# sFMC98_v1.net
KiCad netlist of a schematic drawn in Altium Designer
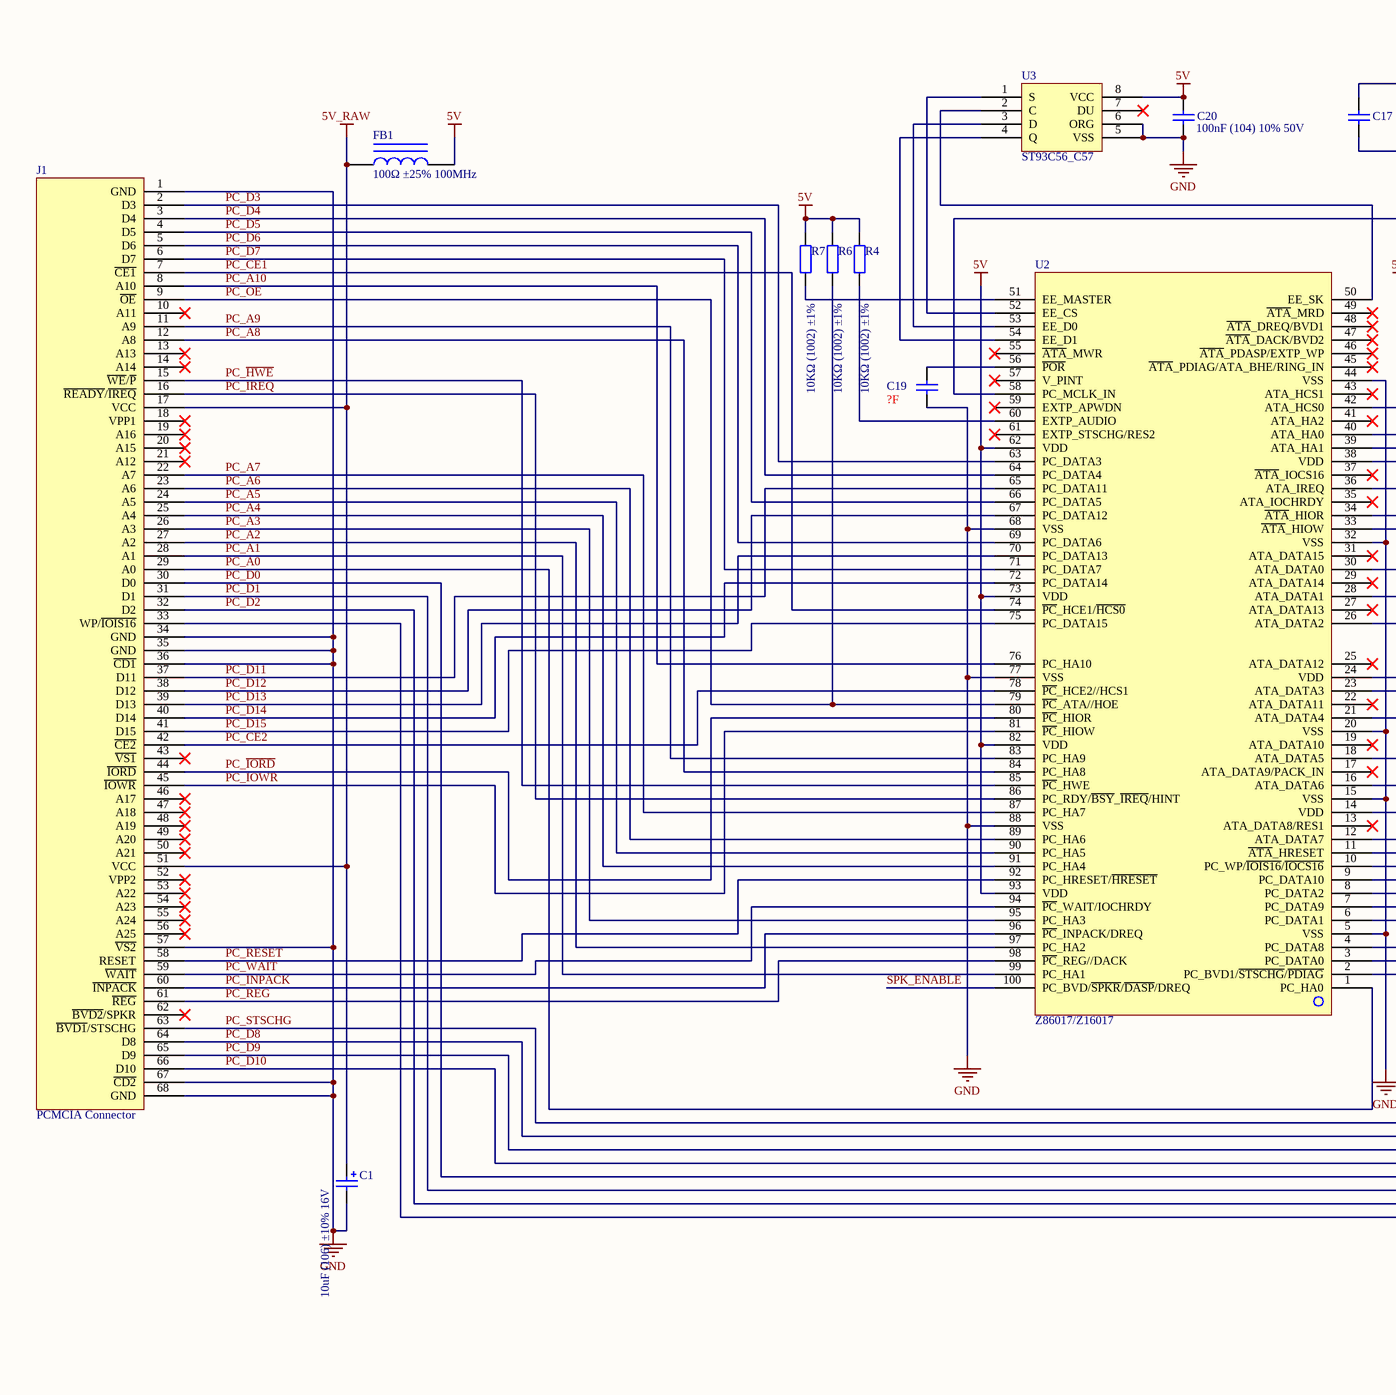
[diagram p0: sFMC98_v1.SchDoc, left]
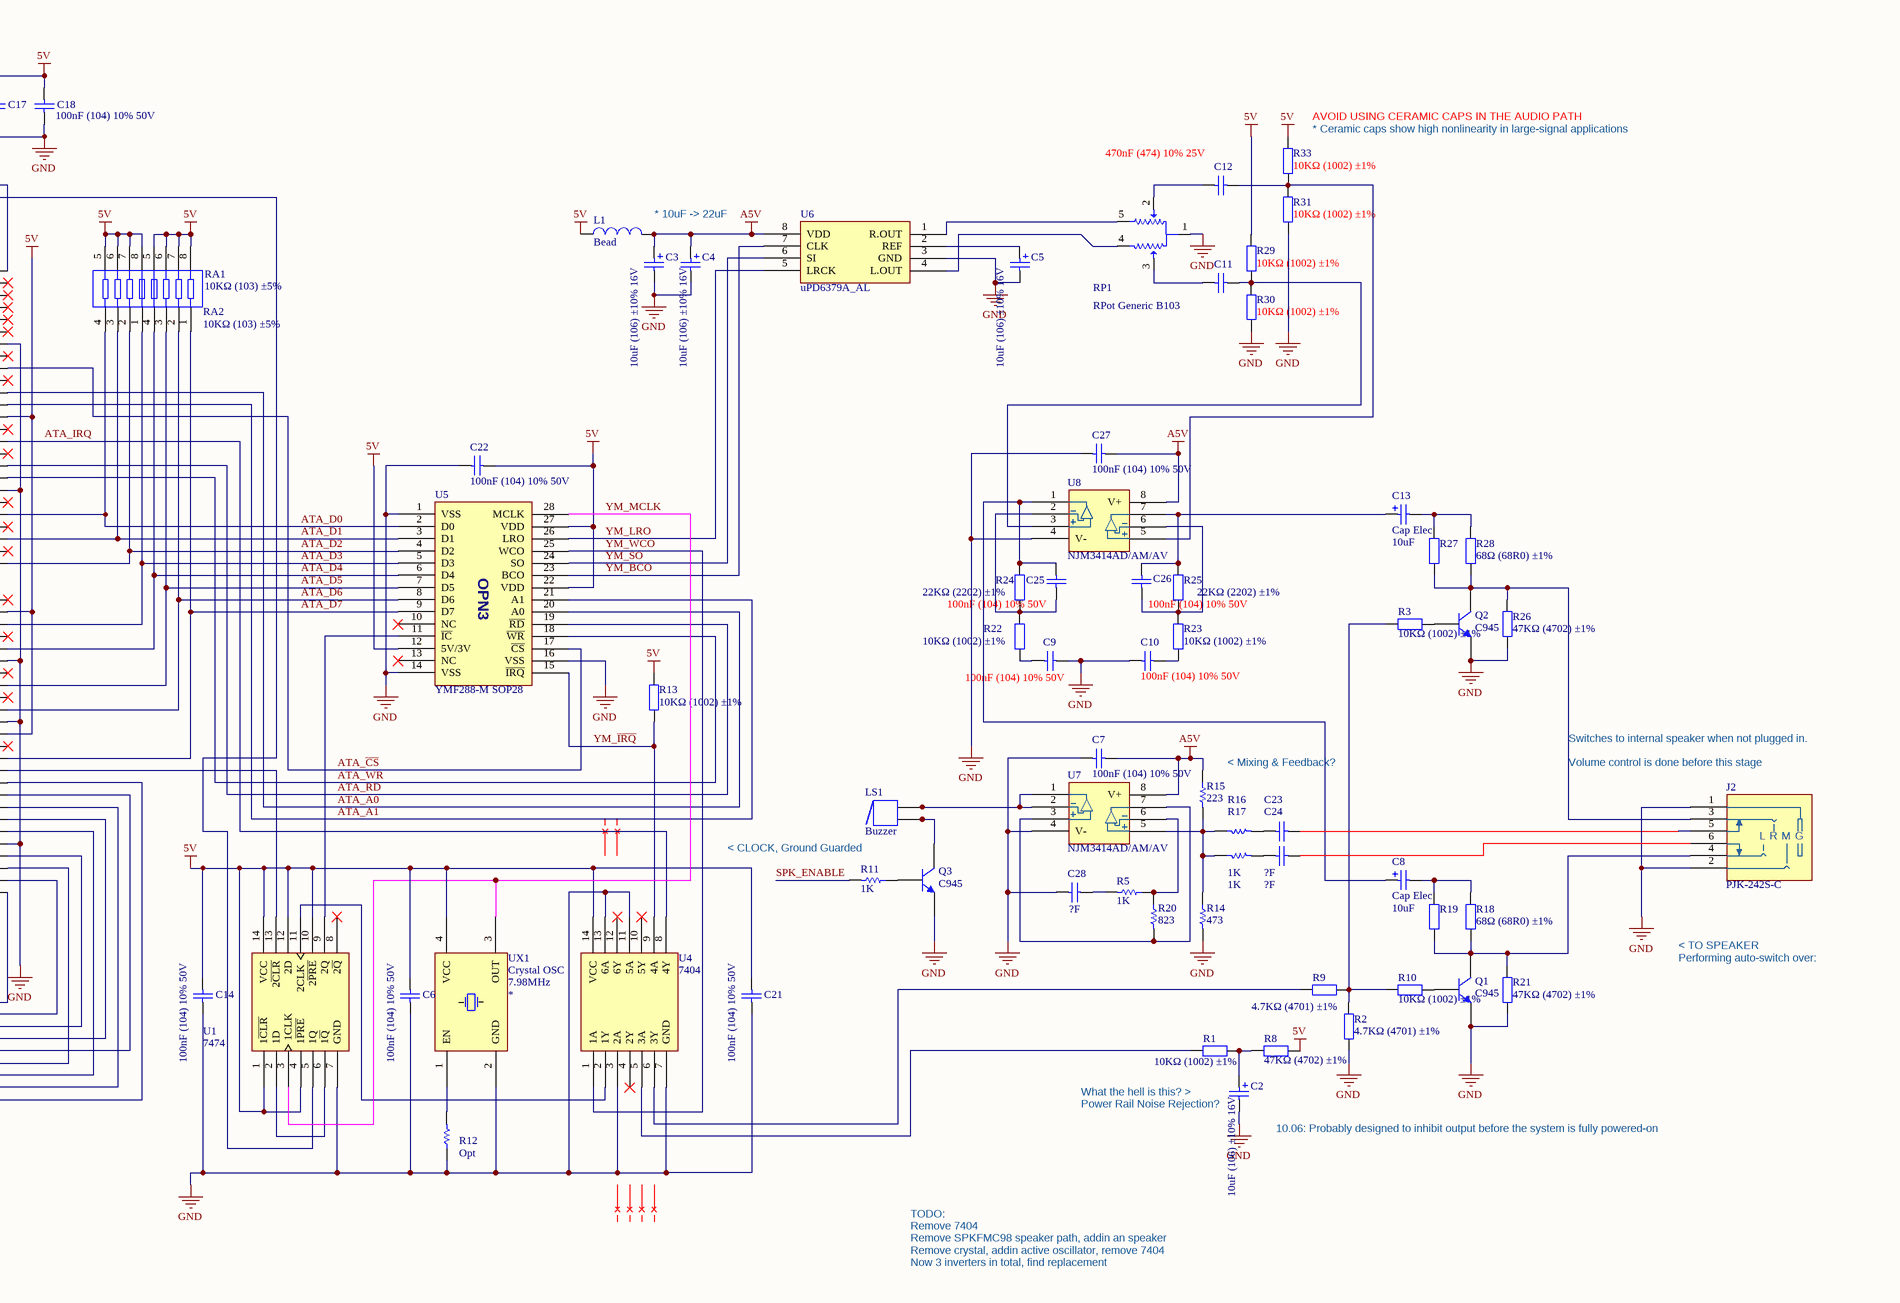
[diagram p1: sFMC98_v1.SchDoc, right]

(export (version "E")
  (design (tool "Eeschema 10.0.6"))
  (components
    (comp (ref "C1")
      (value "10uF (106) ±10% 16V")
      (footprint "CASE-A_3216")
      (description "钽电容")
      (libsource (lib "JLC_Cap") (part "3216 10uF (106) 10% 16V"))
    )
    (comp (ref "C2")
      (value "10uF (106) ±10% 16V")
      (footprint "CASE-A_3216")
      (description "钽电容")
      (libsource (lib "JLC_Cap") (part "3216 10uF (106) 10% 16V"))
    )
    (comp (ref "C3")
      (value "10uF (106) ±10% 16V")
      (footprint "CASE-A_3216")
      (description "钽电容")
      (libsource (lib "JLC_Cap") (part "3216 10uF (106) 10% 16V"))
    )
    (comp (ref "C4")
      (value "10uF (106) ±10% 16V")
      (footprint "CASE-A_3216")
      (description "钽电容")
      (libsource (lib "JLC_Cap") (part "3216 10uF (106) 10% 16V"))
    )
    (comp (ref "C5")
      (value "10uF (106) ±10% 16V")
      (footprint "CASE-A_3216")
      (description "钽电容")
      (libsource (lib "JLC_Cap") (part "3216 10uF (106) 10% 16V"))
    )
    (comp (ref "C6")
      (value "100nF (104) 10% 50V")
      (footprint "0603_C")
      (description "贴片电容")
      (libsource (lib "JLC_Cap") (part "0603 100nF (104) 10% 50V"))
    )
    (comp (ref "C7")
      (value "100nF (104) 10% 50V")
      (footprint "0603_C")
      (description "贴片电容")
      (libsource (lib "JLC_Cap") (part "0603 100nF (104) 10% 50V"))
    )
    (comp (ref "C8")
      (value "Cap Elec")
      (footprint "C-RB-4_5MM_Cutout")
      (description "Polarized Capacitor (Surface Mount)")
      (fields (field (name "ALTIUM_VALUE") "10uF") (field (name "PUBLISHER") "Altium Limited"))
      (libsource (lib "DiscreteRF") (part "Cap Pol3"))
    )
    (comp (ref "C9")
      (value "100nF (104) 10% 50V")
      (footprint "0603_C")
      (description "贴片电容")
      (libsource (lib "JLC_Cap") (part "0603 100nF (104) 10% 50V"))
    )
    (comp (ref "C10")
      (value "100nF (104) 10% 50V")
      (footprint "0603_C")
      (description "贴片电容")
      (libsource (lib "JLC_Cap") (part "0603 100nF (104) 10% 50V"))
    )
    (comp (ref "C11")
      (value "470nF (474) 10% 25V")
      (footprint "0603_C")
      (description "贴片电容")
      (libsource (lib "JLC_Cap") (part "0603 470nF (474) 10% 25V"))
    )
    (comp (ref "C12")
      (value "470nF (474) 10% 25V")
      (footprint "0603_C")
      (description "贴片电容")
      (libsource (lib "JLC_Cap") (part "0603 470nF (474) 10% 25V"))
    )
    (comp (ref "C13")
      (value "Cap Elec")
      (footprint "C-RB-4_5MM_Cutout")
      (description "Polarized Capacitor (Surface Mount)")
      (fields (field (name "ALTIUM_VALUE") "10uF") (field (name "PUBLISHER") "Altium Limited"))
      (libsource (lib "DiscreteRF") (part "Cap Pol3"))
    )
    (comp (ref "C14")
      (value "100nF (104) 10% 50V")
      (footprint "0603_C")
      (description "贴片电容")
      (libsource (lib "JLC_Cap") (part "0603 100nF (104) 10% 50V"))
    )
    (comp (ref "C17")
      (value "100nF (104) 10% 50V")
      (footprint "0603_C")
      (description "贴片电容")
      (libsource (lib "JLC_Cap") (part "0603 100nF (104) 10% 50V"))
    )
    (comp (ref "C18")
      (value "100nF (104) 10% 50V")
      (footprint "0603_C")
      (description "贴片电容")
      (libsource (lib "JLC_Cap") (part "0603 100nF (104) 10% 50V"))
    )
    (comp (ref "C19")
      (value "?F")
      (footprint "CEIA0603X04N")
      (description "Capacitor")
      (fields (field (name "Comment") "Cap") (field (name "PUBLISHER") "Altium Limited"))
      (libsource (lib "DiscreteRF") (part "Cap"))
    )
    (comp (ref "C20")
      (value "100nF (104) 10% 50V")
      (footprint "0603_C")
      (description "贴片电容")
      (libsource (lib "JLC_Cap") (part "0603 100nF (104) 10% 50V"))
    )
    (comp (ref "C21")
      (value "100nF (104) 10% 50V")
      (footprint "0603_C")
      (description "贴片电容")
      (libsource (lib "JLC_Cap") (part "0603 100nF (104) 10% 50V"))
    )
    (comp (ref "C22")
      (value "100nF (104) 10% 50V")
      (footprint "0603_C")
      (description "贴片电容")
      (libsource (lib "JLC_Cap") (part "0603 100nF (104) 10% 50V"))
    )
    (comp (ref "C23")
      (value "?F")
      (footprint "CEIA0603X04N")
      (description "Capacitor")
      (fields (field (name "Comment") "Cap") (field (name "PUBLISHER") "Altium Limited"))
      (libsource (lib "DiscreteRF") (part "Cap"))
    )
    (comp (ref "C24")
      (value "?F")
      (footprint "CEIA0603X04N")
      (description "Capacitor")
      (fields (field (name "Comment") "Cap") (field (name "PUBLISHER") "Altium Limited"))
      (libsource (lib "DiscreteRF") (part "Cap"))
    )
    (comp (ref "C25")
      (value "100nF (104) 10% 50V")
      (footprint "0603_C")
      (description "贴片电容")
      (libsource (lib "JLC_Cap") (part "0603 100nF (104) 10% 50V"))
    )
    (comp (ref "C26")
      (value "100nF (104) 10% 50V")
      (footprint "0603_C")
      (description "贴片电容")
      (libsource (lib "JLC_Cap") (part "0603 100nF (104) 10% 50V"))
    )
    (comp (ref "C27")
      (value "100nF (104) 10% 50V")
      (footprint "0603_C")
      (description "贴片电容")
      (libsource (lib "JLC_Cap") (part "0603 100nF (104) 10% 50V"))
    )
    (comp (ref "C28")
      (value "?F")
      (footprint "CEIA0603X04N")
      (description "Capacitor")
      (fields (field (name "Comment") "Cap") (field (name "PUBLISHER") "Altium Limited"))
      (libsource (lib "DiscreteRF") (part "Cap"))
    )
    (comp (ref "FB1")
      (value "100Ω ±25% 100MHz")
      (footprint "0805_L")
      (description "贴片磁珠")
      (libsource (lib "JLC_IUD") (part "0805 100Ω 25% 100MHz"))
    )
    (comp (ref "J1")
      (value "PCMCIA Connector")
      (footprint "PCF-SMT-K1")
      (libsource (lib "PrimaryLIB1") (part "PCMCIA_Conn"))
    )
    (comp (ref "J2")
      (value "PJK-242S-C")
      (footprint "PJK-242S-C")
      (description "2.5mm Headphone Jack")
      (libsource (lib "PrimaryLIB1") (part "PJK-242S-C"))
    )
    (comp (ref "L1")
      (value "Bead")
      (footprint "L2012X10N_LQW21")
      (description "Inductor")
      (fields (field (name "PUBLISHER") "Altium Limited"))
      (libsource (lib "DiscreteRF") (part "Inductor"))
    )
    (comp (ref "LS1")
      (value "Buzzer")
      (footprint "SPK_PCB_MOUNT")
      (description "Magnetic Transducer Buzzer")
      (fields (field (name "PUBLISHER") "Altium Limited"))
      (libsource (lib "Miscellaneous Devices") (part "Buzzer"))
    )
    (comp (ref "Q1")
      (value "C945")
      (footprint "SOT-23(SOT-23-3)")
      (description "三极管")
      (libsource (lib "JLC_Transistor_NPN") (part "SOT-23 SS8050 Y1"))
    )
    (comp (ref "Q2")
      (value "C945")
      (footprint "SOT-23(SOT-23-3)")
      (description "三极管")
      (libsource (lib "JLC_Transistor_NPN") (part "SOT-23 SS8050 Y1"))
    )
    (comp (ref "Q3")
      (value "C945")
      (footprint "SOT-23(SOT-23-3)")
      (description "三极管")
      (libsource (lib "JLC_Transistor_NPN") (part "SOT-23 SS8050 Y1"))
    )
    (comp (ref "R1")
      (value "10KΩ (1002) ±1%")
      (footprint "0603_R")
      (description "贴片电阻")
      (libsource (lib "") (part "0603 10KΩ (1002) 1%_1"))
    )
    (comp (ref "R2")
      (value "4.7KΩ (4701) ±1%")
      (footprint "0603_R")
      (description "贴片电阻")
      (libsource (lib "JLC_RES") (part "0603 4.7KΩ (4701) 1%"))
    )
    (comp (ref "R3")
      (value "10KΩ (1002) ±1%")
      (footprint "0603_R")
      (description "贴片电阻")
      (libsource (lib "") (part "0603 10KΩ (1002) 1%_1"))
    )
    (comp (ref "R4")
      (value "10KΩ (1002) ±1%")
      (footprint "0603_R")
      (description "贴片电阻")
      (libsource (lib "JLC_RES") (part "0603 10KΩ (1002) 1%"))
    )
    (comp (ref "R5")
      (value "1K")
      (footprint "REIA0603X04N")
      (description "Resistor")
      (fields (field (name "Comment") "Res1") (field (name "PUBLISHER") "Altium Limited"))
      (libsource (lib "DiscreteRF") (part "Res1"))
    )
    (comp (ref "R6")
      (value "10KΩ (1002) ±1%")
      (footprint "0603_R")
      (description "贴片电阻")
      (libsource (lib "JLC_RES") (part "0603 10KΩ (1002) 1%"))
    )
    (comp (ref "R7")
      (value "10KΩ (1002) ±1%")
      (footprint "0603_R")
      (description "贴片电阻")
      (libsource (lib "JLC_RES") (part "0603 10KΩ (1002) 1%"))
    )
    (comp (ref "R8")
      (value "47KΩ (4702) ±1%")
      (footprint "0603_R")
      (description "贴片电阻")
      (libsource (lib "") (part "0603 47KΩ (4702) 1%_1"))
    )
    (comp (ref "R9")
      (value "4.7KΩ (4701) ±1%")
      (footprint "0603_R")
      (description "贴片电阻")
      (libsource (lib "") (part "0603 4.7KΩ (4701) 1%_1"))
    )
    (comp (ref "R10")
      (value "10KΩ (1002) ±1%")
      (footprint "0603_R")
      (description "贴片电阻")
      (libsource (lib "") (part "0603 10KΩ (1002) 1%_1"))
    )
    (comp (ref "R11")
      (value "1K")
      (footprint "REIA0603X04N")
      (description "Resistor")
      (fields (field (name "Comment") "Res1") (field (name "PUBLISHER") "Altium Limited"))
      (libsource (lib "DiscreteRF") (part "Res1"))
    )
    (comp (ref "R12")
      (value "Opt")
      (footprint "REIA0603X04N")
      (description "Resistor")
      (fields (field (name "Comment") "Res1") (field (name "PUBLISHER") "Altium Limited"))
      (libsource (lib "DiscreteRF") (part "Res1"))
    )
    (comp (ref "R13")
      (value "10KΩ (1002) ±1%")
      (footprint "0603_R")
      (description "贴片电阻")
      (libsource (lib "JLC_RES") (part "0603 10KΩ (1002) 1%"))
    )
    (comp (ref "R14")
      (value "473")
      (footprint "REIA0603X04N")
      (description "Resistor")
      (fields (field (name "Comment") "Res1") (field (name "PUBLISHER") "Altium Limited"))
      (libsource (lib "DiscreteRF") (part "Res1"))
    )
    (comp (ref "R15")
      (value "223")
      (footprint "REIA0603X04N")
      (description "Resistor")
      (fields (field (name "Comment") "Res1") (field (name "PUBLISHER") "Altium Limited"))
      (libsource (lib "DiscreteRF") (part "Res1"))
    )
    (comp (ref "R16")
      (value "1K")
      (footprint "REIA0603X04N")
      (description "Resistor")
      (fields (field (name "Comment") "Res1") (field (name "PUBLISHER") "Altium Limited"))
      (libsource (lib "DiscreteRF") (part "Res1"))
    )
    (comp (ref "R17")
      (value "1K")
      (footprint "REIA0603X04N")
      (description "Resistor")
      (fields (field (name "Comment") "Res1") (field (name "PUBLISHER") "Altium Limited"))
      (libsource (lib "DiscreteRF") (part "Res1"))
    )
    (comp (ref "R18")
      (value "68Ω (68R0) ±1%")
      (footprint "0603_R")
      (description "贴片电阻")
      (libsource (lib "JLC_RES") (part "0603 68Ω (68R0) 1%"))
    )
    (comp (ref "R19")
      (value "68Ω (68R0) ±1%")
      (footprint "0603_R")
      (description "贴片电阻")
      (libsource (lib "JLC_RES") (part "0603 68Ω (68R0) 1%"))
    )
    (comp (ref "R20")
      (value "823")
      (footprint "REIA0603X04N")
      (description "Resistor")
      (fields (field (name "Comment") "Res1") (field (name "PUBLISHER") "Altium Limited"))
      (libsource (lib "DiscreteRF") (part "Res1"))
    )
    (comp (ref "R21")
      (value "47KΩ (4702) ±1%")
      (footprint "0603_R")
      (description "贴片电阻")
      (libsource (lib "JLC_RES") (part "0603 47KΩ (4702) 1%"))
    )
    (comp (ref "R22")
      (value "10KΩ (1002) ±1%")
      (footprint "0603_R")
      (description "贴片电阻")
      (libsource (lib "JLC_RES") (part "0603 10KΩ (1002) 1%"))
    )
    (comp (ref "R23")
      (value "10KΩ (1002) ±1%")
      (footprint "0603_R")
      (description "贴片电阻")
      (libsource (lib "JLC_RES") (part "0603 10KΩ (1002) 1%"))
    )
    (comp (ref "R24")
      (value "22KΩ (2202) ±1%")
      (footprint "0603_R")
      (description "贴片电阻")
      (libsource (lib "JLC_RES") (part "0603 22KΩ (2202) 1%"))
    )
    (comp (ref "R25")
      (value "22KΩ (2202) ±1%")
      (footprint "0603_R")
      (description "贴片电阻")
      (libsource (lib "JLC_RES") (part "0603 22KΩ (2202) 1%"))
    )
    (comp (ref "R26")
      (value "47KΩ (4702) ±1%")
      (footprint "0603_R")
      (description "贴片电阻")
      (libsource (lib "JLC_RES") (part "0603 47KΩ (4702) 1%"))
    )
    (comp (ref "R27")
      (value "68Ω (68R0) ±1%")
      (footprint "0603_R")
      (description "贴片电阻")
      (libsource (lib "JLC_RES") (part "0603 68Ω (68R0) 1%"))
    )
    (comp (ref "R28")
      (value "68Ω (68R0) ±1%")
      (footprint "0603_R")
      (description "贴片电阻")
      (libsource (lib "JLC_RES") (part "0603 68Ω (68R0) 1%"))
    )
    (comp (ref "R29")
      (value "10KΩ (1002) ±1%")
      (footprint "0603_R")
      (description "贴片电阻")
      (libsource (lib "JLC_RES") (part "0603 10KΩ (1002) 1%"))
    )
    (comp (ref "R30")
      (value "10KΩ (1002) ±1%")
      (footprint "0603_R")
      (description "贴片电阻")
      (libsource (lib "JLC_RES") (part "0603 10KΩ (1002) 1%"))
    )
    (comp (ref "R31")
      (value "10KΩ (1002) ±1%")
      (footprint "0603_R")
      (description "贴片电阻")
      (libsource (lib "JLC_RES") (part "0603 10KΩ (1002) 1%"))
    )
    (comp (ref "R33")
      (value "10KΩ (1002) ±1%")
      (footprint "0603_R")
      (description "贴片电阻")
      (libsource (lib "JLC_RES") (part "0603 10KΩ (1002) 1%"))
    )
    (comp (ref "RA1")
      (value "10KΩ (103) ±5%")
      (footprint "0603_Rx4")
      (description "贴片排阻")
      (libsource (lib "JLC_RES") (part "0603*4  10KΩ (103) 5%"))
    )
    (comp (ref "RA2")
      (value "10KΩ (103) ±5%")
      (footprint "0603_Rx4")
      (description "贴片排阻")
      (libsource (lib "JLC_RES") (part "0603*4  10KΩ (103) 5%"))
    )
    (comp (ref "RP1")
      (value "RPot Generic B103")
      (footprint "RPot_RK10J12E_ALPS")
      (libsource (lib "PrimaryLIB1") (part "RPot_Generic_Bxxx"))
    )
    (comp (ref "U1")
      (value "7474")
      (footprint "TSSOP14_TSOP65P640X120-14N")
      (description "Dual D-Type Positive-Edge-Triggered Flip-Flops With Preset And Clear")
      (libsource (lib "7400") (part "7474_J_N_1"))
    )
    (comp (ref "U2")
      (value "Z86017/Z16017")
      (footprint "VQFP100_TSQFP50P1600X1600X160-100N")
      (libsource (lib "PrimaryLIB1") (part "ZX6017"))
    )
    (comp (ref "U3")
      (value "ST93C56_C57")
      (footprint "SOIC-8 NB")
      (description "2K (128 x 16 or 256 x 8) SERIAL MICROWIRE EEPROM")
      (libsource (lib "PrimaryLIB1") (part "ST93C56_C57"))
    )
    (comp (ref "U4")
      (value "7404")
      (footprint "TSSOP14_TSOP65P640X120-14N")
      (description "Hex Inverter")
      (libsource (lib "7400") (part "7404_J_N_1"))
    )
    (comp (ref "U5")
      (value "YMF288-M SOP28")
      (footprint "SOP127P1030X265-28N")
      (libsource (lib "Audio") (part "YMF288_M"))
    )
    (comp (ref "U6")
      (value "uPD6379A_AL")
      (footprint "DMP8_SOIC127P680X175-8N")
      (description "2-CHANNEL 16-BIT D/A CONVERTER FOR AUDIO APPLICATION")
      (libsource (lib "Audio") (part "uPD6379A_AL"))
    )
    (comp (ref "U7")
      (value "NJM3414AD/AM/AV")
      (footprint "DMP8_SOIC127P680X175-8N")
      (description "Single-Supply Dual High Current Operational Amplifier")
      (libsource (lib "PrimaryLIB1") (part "NJM3414AD_AM_AV_1"))
    )
    (comp (ref "U8")
      (value "NJM3414AD/AM/AV")
      (footprint "DMP8_SOIC127P680X175-8N")
      (description "Single-Supply Dual High Current Operational Amplifier")
      (libsource (lib "PrimaryLIB1") (part "NJM3414AD_AM_AV_1"))
    )
    (comp (ref "UX1")
      (value "Crystal OSC")
      (footprint "SMD-3225_4P")
      (fields (field (name "FREQ") "7.98MHz") (field (name "TYPE") "*"))
      (libsource (lib "PrimaryLIB1") (part "XTAL_OSC"))
    )
  )
  (nets
    (net (code "1") (name "/ATA_A0") (class "Default")
      (node (ref "U2") (pin "40") (pinfunction "ATA_HA0_40") (pintype "passive"))
      (node (ref "U5") (pin "20") (pinfunction "A0_20") (pintype "passive"))
    )
    (net (code "2") (name "/ATA_A1") (class "Default")
      (node (ref "U2") (pin "39") (pinfunction "ATA_HA1_39") (pintype "passive"))
      (node (ref "U5") (pin "21") (pinfunction "A1_21") (pintype "passive"))
    )
    (net (code "3") (name "/ATA_D0") (class "Default")
      (node (ref "RA2") (pin "4") (pinfunction "4_4") (pintype "passive"))
      (node (ref "U2") (pin "30") (pinfunction "ATA_DATA0_30") (pintype "passive"))
      (node (ref "U5") (pin "2") (pinfunction "D0_2") (pintype "passive"))
    )
    (net (code "4") (name "/ATA_D1") (class "Default")
      (node (ref "RA2") (pin "3") (pinfunction "3_3") (pintype "passive"))
      (node (ref "U2") (pin "28") (pinfunction "ATA_DATA1_28") (pintype "passive"))
      (node (ref "U5") (pin "3") (pinfunction "D1_3") (pintype "passive"))
    )
    (net (code "5") (name "/ATA_D2") (class "Default")
      (node (ref "RA2") (pin "2") (pinfunction "2_2") (pintype "passive"))
      (node (ref "U2") (pin "26") (pinfunction "ATA_DATA2_26") (pintype "passive"))
      (node (ref "U5") (pin "4") (pinfunction "D2_4") (pintype "passive"))
    )
    (net (code "6") (name "/ATA_D3") (class "Default")
      (node (ref "RA2") (pin "1") (pinfunction "1_1") (pintype "passive"))
      (node (ref "U2") (pin "23") (pinfunction "ATA_DATA3_23") (pintype "passive"))
      (node (ref "U5") (pin "5") (pinfunction "D3_5") (pintype "passive"))
    )
    (net (code "7") (name "/ATA_D4") (class "Default")
      (node (ref "RA1") (pin "4") (pinfunction "4_4") (pintype "passive"))
      (node (ref "U2") (pin "21") (pinfunction "ATA_DATA4_21") (pintype "passive"))
      (node (ref "U5") (pin "6") (pinfunction "D4_6") (pintype "passive"))
    )
    (net (code "8") (name "/ATA_D5") (class "Default")
      (node (ref "RA1") (pin "3") (pinfunction "3_3") (pintype "passive"))
      (node (ref "U2") (pin "18") (pinfunction "ATA_DATA5_18") (pintype "passive"))
      (node (ref "U5") (pin "7") (pinfunction "D5_7") (pintype "passive"))
    )
    (net (code "9") (name "/ATA_D6") (class "Default")
      (node (ref "RA1") (pin "2") (pinfunction "2_2") (pintype "passive"))
      (node (ref "U2") (pin "16") (pinfunction "ATA_DATA6_16") (pintype "passive"))
      (node (ref "U5") (pin "8") (pinfunction "D6_8") (pintype "passive"))
    )
    (net (code "10") (name "/ATA_D7") (class "Default")
      (node (ref "RA1") (pin "1") (pinfunction "1_1") (pintype "passive"))
      (node (ref "U2") (pin "12") (pinfunction "ATA_DATA7_12") (pintype "passive"))
      (node (ref "U5") (pin "9") (pinfunction "D7_9") (pintype "passive"))
    )
    (net (code "11") (name "/ATA_IRQ") (class "Default")
      (node (ref "U2") (pin "36") (pinfunction "ATA_IREQ_36") (pintype "passive"))
      (node (ref "U4") (pin "8") (pinfunction "4Y_8") (pintype "passive"))
    )
    (net (code "12") (name "/ATA_~{CS}") (class "Default")
      (node (ref "U2") (pin "42") (pinfunction "ATA_HCS0_42") (pintype "passive"))
      (node (ref "U5") (pin "17") (pinfunction "~{CS}_17") (pintype "passive"))
    )
    (net (code "13") (name "/ATA_~{RD}") (class "Default")
      (node (ref "U2") (pin "34") (pinfunction "~{ATA}_HIOR_34") (pintype "passive"))
      (node (ref "U5") (pin "19") (pinfunction "~{RD}_19") (pintype "passive"))
    )
    (net (code "14") (name "/ATA_~{WR}") (class "Default")
      (node (ref "U2") (pin "33") (pinfunction "~{ATA}_HIOW_33") (pintype "passive"))
      (node (ref "U5") (pin "18") (pinfunction "~{WR}_18") (pintype "passive"))
    )
    (net (code "15") (name "/PC_A0") (class "Default")
      (node (ref "J1") (pin "29") (pinfunction "A0_29") (pintype "passive"))
      (node (ref "U2") (pin "1") (pinfunction "PC_HA0_1") (pintype "passive"))
    )
    (net (code "16") (name "/PC_A1") (class "Default")
      (node (ref "J1") (pin "28") (pinfunction "A1_28") (pintype "passive"))
      (node (ref "U2") (pin "99") (pinfunction "PC_HA1_99") (pintype "passive"))
    )
    (net (code "17") (name "/PC_A2") (class "Default")
      (node (ref "J1") (pin "27") (pinfunction "A2_27") (pintype "passive"))
      (node (ref "U2") (pin "97") (pinfunction "PC_HA2_97") (pintype "passive"))
    )
    (net (code "18") (name "/PC_A3") (class "Default")
      (node (ref "J1") (pin "26") (pinfunction "A3_26") (pintype "passive"))
      (node (ref "U2") (pin "95") (pinfunction "PC_HA3_95") (pintype "passive"))
    )
    (net (code "19") (name "/PC_A4") (class "Default")
      (node (ref "J1") (pin "25") (pinfunction "A4_25") (pintype "passive"))
      (node (ref "U2") (pin "91") (pinfunction "PC_HA4_91") (pintype "passive"))
    )
    (net (code "20") (name "/PC_A5") (class "Default")
      (node (ref "J1") (pin "24") (pinfunction "A5_24") (pintype "passive"))
      (node (ref "U2") (pin "90") (pinfunction "PC_HA5_90") (pintype "passive"))
    )
    (net (code "21") (name "/PC_A6") (class "Default")
      (node (ref "J1") (pin "23") (pinfunction "A6_23") (pintype "passive"))
      (node (ref "U2") (pin "89") (pinfunction "PC_HA6_89") (pintype "passive"))
    )
    (net (code "22") (name "/PC_A7") (class "Default")
      (node (ref "J1") (pin "22") (pinfunction "A7_22") (pintype "passive"))
      (node (ref "U2") (pin "87") (pinfunction "PC_HA7_87") (pintype "passive"))
    )
    (net (code "23") (name "/PC_A8") (class "Default")
      (node (ref "J1") (pin "12") (pinfunction "A8_12") (pintype "passive"))
      (node (ref "U2") (pin "84") (pinfunction "PC_HA8_84") (pintype "passive"))
    )
    (net (code "24") (name "/PC_A9") (class "Default")
      (node (ref "J1") (pin "11") (pinfunction "A9_11") (pintype "passive"))
      (node (ref "U2") (pin "83") (pinfunction "PC_HA9_83") (pintype "passive"))
    )
    (net (code "25") (name "/PC_A10") (class "Default")
      (node (ref "J1") (pin "8") (pinfunction "A10_8") (pintype "passive"))
      (node (ref "U2") (pin "76") (pinfunction "PC_HA10_76") (pintype "passive"))
    )
    (net (code "26") (name "/PC_D0") (class "Default")
      (node (ref "J1") (pin "30") (pinfunction "D0_30") (pintype "passive"))
      (node (ref "U2") (pin "3") (pinfunction "PC_DATA0_3") (pintype "passive"))
    )
    (net (code "27") (name "/PC_D1") (class "Default")
      (node (ref "J1") (pin "31") (pinfunction "D1_31") (pintype "passive"))
      (node (ref "U2") (pin "6") (pinfunction "PC_DATA1_6") (pintype "passive"))
    )
    (net (code "28") (name "/PC_D2") (class "Default")
      (node (ref "J1") (pin "32") (pinfunction "D2_32") (pintype "passive"))
      (node (ref "U2") (pin "8") (pinfunction "PC_DATA2_8") (pintype "passive"))
    )
    (net (code "29") (name "/PC_D3") (class "Default")
      (node (ref "J1") (pin "2") (pinfunction "D3_2") (pintype "passive"))
      (node (ref "U2") (pin "63") (pinfunction "PC_DATA3_63") (pintype "passive"))
    )
    (net (code "30") (name "/PC_D4") (class "Default")
      (node (ref "J1") (pin "3") (pinfunction "D4_3") (pintype "passive"))
      (node (ref "U2") (pin "64") (pinfunction "PC_DATA4_64") (pintype "passive"))
    )
    (net (code "31") (name "/PC_D5") (class "Default")
      (node (ref "J1") (pin "4") (pinfunction "D5_4") (pintype "passive"))
      (node (ref "U2") (pin "66") (pinfunction "PC_DATA5_66") (pintype "passive"))
    )
    (net (code "32") (name "/PC_D6") (class "Default")
      (node (ref "J1") (pin "5") (pinfunction "D6_5") (pintype "passive"))
      (node (ref "U2") (pin "69") (pinfunction "PC_DATA6_69") (pintype "passive"))
    )
    (net (code "33") (name "/PC_D7") (class "Default")
      (node (ref "J1") (pin "6") (pinfunction "D7_6") (pintype "passive"))
      (node (ref "U2") (pin "71") (pinfunction "PC_DATA7_71") (pintype "passive"))
    )
    (net (code "34") (name "/PC_D8") (class "Default")
      (node (ref "J1") (pin "64") (pinfunction "D8_64") (pintype "passive"))
      (node (ref "U2") (pin "4") (pinfunction "PC_DATA8_4") (pintype "passive"))
    )
    (net (code "35") (name "/PC_D9") (class "Default")
      (node (ref "J1") (pin "65") (pinfunction "D9_65") (pintype "passive"))
      (node (ref "U2") (pin "7") (pinfunction "PC_DATA9_7") (pintype "passive"))
    )
    (net (code "36") (name "/PC_D10") (class "Default")
      (node (ref "J1") (pin "66") (pinfunction "D10_66") (pintype "passive"))
      (node (ref "U2") (pin "9") (pinfunction "PC_DATA10_9") (pintype "passive"))
    )
    (net (code "37") (name "/PC_D11") (class "Default")
      (node (ref "J1") (pin "37") (pinfunction "D11_37") (pintype "passive"))
      (node (ref "U2") (pin "65") (pinfunction "PC_DATA11_65") (pintype "passive"))
    )
    (net (code "38") (name "/PC_D12") (class "Default")
      (node (ref "J1") (pin "38") (pinfunction "D12_38") (pintype "passive"))
      (node (ref "U2") (pin "67") (pinfunction "PC_DATA12_67") (pintype "passive"))
    )
    (net (code "39") (name "/PC_D13") (class "Default")
      (node (ref "J1") (pin "39") (pinfunction "D13_39") (pintype "passive"))
      (node (ref "U2") (pin "70") (pinfunction "PC_DATA13_70") (pintype "passive"))
    )
    (net (code "40") (name "/PC_D14") (class "Default")
      (node (ref "J1") (pin "40") (pinfunction "D14_40") (pintype "passive"))
      (node (ref "U2") (pin "72") (pinfunction "PC_DATA14_72") (pintype "passive"))
    )
    (net (code "41") (name "/PC_D15") (class "Default")
      (node (ref "J1") (pin "41") (pinfunction "D15_41") (pintype "passive"))
      (node (ref "U2") (pin "75") (pinfunction "PC_DATA15_75") (pintype "passive"))
    )
    (net (code "42") (name "/PC_RESET") (class "Default")
      (node (ref "J1") (pin "58") (pinfunction "RESET_58") (pintype "passive"))
      (node (ref "U2") (pin "92") (pinfunction "PC_HRESET/~{HRESET}_92") (pintype "passive"))
    )
    (net (code "43") (name "/PC_STSCHG") (class "Default")
      (node (ref "J1") (pin "63") (pinfunction "~{BVD1}/STSCHG_63") (pintype "passive"))
      (node (ref "U2") (pin "2") (pinfunction "PC_BVD1/~{STSCHG}/~{PDIAG}_2") (pintype "passive"))
    )
    (net (code "44") (name "/PC_~{CE1}") (class "Default")
      (node (ref "J1") (pin "7") (pinfunction "~{CE1}_7") (pintype "passive"))
      (node (ref "U2") (pin "74") (pinfunction "~{PC}_HCE1/~{HCS0}_74") (pintype "passive"))
    )
    (net (code "45") (name "/PC_~{CE2}") (class "Default")
      (node (ref "J1") (pin "42") (pinfunction "~{CE2}_42") (pintype "passive"))
      (node (ref "U2") (pin "78") (pinfunction "~{PC}_HCE2//HCS1_78") (pintype "passive"))
    )
    (net (code "46") (name "/PC_~{HWE}") (class "Default")
      (node (ref "J1") (pin "15") (pinfunction "~{WE}/~{P}_15") (pintype "passive"))
      (node (ref "U2") (pin "85") (pinfunction "~{PC}_HWE_85") (pintype "passive"))
    )
    (net (code "47") (name "/PC_~{INPACK}") (class "Default")
      (node (ref "J1") (pin "60") (pinfunction "~{INPACK}_60") (pintype "passive"))
      (node (ref "U2") (pin "96") (pinfunction "~{PC}_INPACK/DREQ_96") (pintype "passive"))
    )
    (net (code "48") (name "/PC_~{IORD}") (class "Default")
      (node (ref "J1") (pin "44") (pinfunction "~{IORD}_44") (pintype "passive"))
      (node (ref "U2") (pin "80") (pinfunction "~{PC}_HIOR_80") (pintype "passive"))
    )
    (net (code "49") (name "/PC_~{IOWR}") (class "Default")
      (node (ref "J1") (pin "45") (pinfunction "~{IOWR}_45") (pintype "passive"))
      (node (ref "U2") (pin "81") (pinfunction "~{PC}_HIOW_81") (pintype "passive"))
    )
    (net (code "50") (name "/PC_~{IREQ}") (class "Default")
      (node (ref "J1") (pin "16") (pinfunction "~{READY}/~{IREQ}_16") (pintype "passive"))
      (node (ref "U2") (pin "86") (pinfunction "PC_RDY/~{BSY}_~{IREQ}/HINT_86") (pintype "passive"))
    )
    (net (code "51") (name "/PC_~{OE}") (class "Default")
      (node (ref "J1") (pin "9") (pinfunction "~{OE}_9") (pintype "passive"))
      (node (ref "R6") (pin "1") (pinfunction "1_1") (pintype "passive"))
      (node (ref "U2") (pin "79") (pinfunction "~{PC}_ATA//HOE_79") (pintype "passive"))
    )
    (net (code "52") (name "/PC_~{REG}") (class "Default")
      (node (ref "J1") (pin "61") (pinfunction "~{REG}_61") (pintype "passive"))
      (node (ref "U2") (pin "98") (pinfunction "~{PC}_REG//DACK_98") (pintype "passive"))
    )
    (net (code "53") (name "/PC_~{WAIT}") (class "Default")
      (node (ref "J1") (pin "59") (pinfunction "~{WAIT}_59") (pintype "passive"))
      (node (ref "U2") (pin "94") (pinfunction "~{PC}_WAIT/IOCHRDY_94") (pintype "passive"))
    )
    (net (code "54") (name "/SPK_ENABLE") (class "Default")
      (node (ref "R11") (pin "2") (pinfunction "2_2") (pintype "passive"))
      (node (ref "U2") (pin "100") (pinfunction "PC_BVD/~{SPKR}/~{DASP}/DREQ_100") (pintype "passive"))
    )
    (net (code "55") (name "/YM_BCO") (class "Default")
      (node (ref "U5") (pin "23") (pinfunction "BCO_23") (pintype "passive"))
      (node (ref "U6") (pin "7") (pinfunction "CLK_7") (pintype "passive"))
    )
    (net (code "56") (name "/YM_LRO") (class "Default")
      (node (ref "U5") (pin "26") (pinfunction "LRO_26") (pintype "passive"))
      (node (ref "U6") (pin "5") (pinfunction "LRCK_5") (pintype "passive"))
    )
    (net (code "57") (name "/YM_MCLK") (class "Default")
      (node (ref "U1") (pin "3") (pinfunction "1CLK_3") (pintype "passive"))
      (node (ref "U5") (pin "28") (pinfunction "MCLK_28") (pintype "passive"))
      (node (ref "UX1") (pin "3") (pinfunction "OUT_3") (pintype "passive"))
    )
    (net (code "58") (name "/YM_SO") (class "Default")
      (node (ref "U5") (pin "24") (pinfunction "SO_24") (pintype "passive"))
      (node (ref "U6") (pin "6") (pinfunction "SI_6") (pintype "passive"))
    )
    (net (code "59") (name "/YM_WCO") (class "Default")
      (node (ref "U4") (pin "1") (pinfunction "1A_1") (pintype "passive"))
      (node (ref "U5") (pin "25") (pinfunction "WCO_25") (pintype "passive"))
    )
    (net (code "60") (name "/YM_~{IRQ}") (class "Default")
      (node (ref "R13") (pin "1") (pinfunction "1_1") (pintype "passive"))
      (node (ref "U4") (pin "9") (pinfunction "4A_9") (pintype "passive"))
      (node (ref "U5") (pin "15") (pinfunction "~{IRQ}_15") (pintype "passive"))
    )
    (net (code "61") (name "5V") (class "Default")
      (node (ref "C14") (pin "2") (pinfunction "2_2") (pintype "passive"))
      (node (ref "C17") (pin "2") (pinfunction "2_2") (pintype "passive"))
      (node (ref "C18") (pin "2") (pinfunction "2_2") (pintype "passive"))
      (node (ref "C20") (pin "2") (pinfunction "2_2") (pintype "passive"))
      (node (ref "C21") (pin "2") (pinfunction "2_2") (pintype "passive"))
      (node (ref "C22") (pin "1") (pinfunction "1_1") (pintype "passive"))
      (node (ref "C6") (pin "2") (pinfunction "2_2") (pintype "passive"))
      (node (ref "FB1") (pin "2") (pinfunction "2_2") (pintype "passive"))
      (node (ref "L1") (pin "2") (pinfunction "2_2") (pintype "passive"))
      (node (ref "R13") (pin "2") (pinfunction "2_2") (pintype "passive"))
      (node (ref "R29") (pin "2") (pinfunction "2_2") (pintype "passive"))
      (node (ref "R33") (pin "2") (pinfunction "2_2") (pintype "passive"))
      (node (ref "R4") (pin "2") (pinfunction "2_2") (pintype "passive"))
      (node (ref "R6") (pin "2") (pinfunction "2_2") (pintype "passive"))
      (node (ref "R7") (pin "2") (pinfunction "2_2") (pintype "passive"))
      (node (ref "R8") (pin "1") (pinfunction "1_1") (pintype "passive"))
      (node (ref "RA1") (pin "5") (pinfunction "5_5") (pintype "passive"))
      (node (ref "RA1") (pin "6") (pinfunction "6_6") (pintype "passive"))
      (node (ref "RA1") (pin "7") (pinfunction "7_7") (pintype "passive"))
      (node (ref "RA1") (pin "8") (pinfunction "8_8") (pintype "passive"))
      (node (ref "RA2") (pin "5") (pinfunction "5_5") (pintype "passive"))
      (node (ref "RA2") (pin "6") (pinfunction "6_6") (pintype "passive"))
      (node (ref "RA2") (pin "7") (pinfunction "7_7") (pintype "passive"))
      (node (ref "RA2") (pin "8") (pinfunction "8_8") (pintype "passive"))
      (node (ref "U1") (pin "1") (pinfunction "1~{CLR}_1") (pintype "passive"))
      (node (ref "U1") (pin "10") (pinfunction "2~{PRE}_10") (pintype "passive"))
      (node (ref "U1") (pin "12") (pinfunction "2D_12") (pintype "passive"))
      (node (ref "U1") (pin "14") (pinfunction "VCC_14") (pintype "passive"))
      (node (ref "U1") (pin "4") (pinfunction "1~{PRE}_4") (pintype "passive"))
      (node (ref "U2") (pin "14") (pinfunction "VDD_14") (pintype "passive"))
      (node (ref "U2") (pin "24") (pinfunction "VDD_24") (pintype "passive"))
      (node (ref "U2") (pin "38") (pinfunction "VDD_38") (pintype "passive"))
      (node (ref "U2") (pin "62") (pinfunction "VDD_62") (pintype "passive"))
      (node (ref "U2") (pin "73") (pinfunction "VDD_73") (pintype "passive"))
      (node (ref "U2") (pin "82") (pinfunction "VDD_82") (pintype "passive"))
      (node (ref "U2") (pin "93") (pinfunction "VDD_93") (pintype "passive"))
      (node (ref "U3") (pin "8") (pinfunction "VCC_8") (pintype "passive"))
      (node (ref "U4") (pin "14") (pinfunction "VCC_14") (pintype "passive"))
      (node (ref "U5") (pin "12") (pinfunction "5V/3V_12") (pintype "passive"))
      (node (ref "U5") (pin "22") (pinfunction "VDD_22") (pintype "passive"))
      (node (ref "U5") (pin "27") (pinfunction "VDD_27") (pintype "passive"))
      (node (ref "UX1") (pin "4") (pinfunction "VCC_4") (pintype "passive"))
    )
    (net (code "62") (name "5V_RAW") (class "Default")
      (node (ref "C1") (pin "1") (pinfunction "1_1") (pintype "passive"))
      (node (ref "FB1") (pin "1") (pinfunction "1_1") (pintype "passive"))
      (node (ref "J1") (pin "17") (pinfunction "VCC_17") (pintype "passive"))
      (node (ref "J1") (pin "51") (pinfunction "VCC_51") (pintype "passive"))
    )
    (net (code "63") (name "A5V") (class "Default")
      (node (ref "C27") (pin "1") (pinfunction "1_1") (pintype "passive"))
      (node (ref "C3") (pin "1") (pinfunction "1_1") (pintype "passive"))
      (node (ref "C4") (pin "1") (pinfunction "1_1") (pintype "passive"))
      (node (ref "C7") (pin "1") (pinfunction "1_1") (pintype "passive"))
      (node (ref "L1") (pin "1") (pinfunction "1_1") (pintype "passive"))
      (node (ref "R15") (pin "1") (pinfunction "1_1") (pintype "passive"))
      (node (ref "U6") (pin "8") (pinfunction "VDD_8") (pintype "passive"))
      (node (ref "U7") (pin "8") (pinfunction "V+_8") (pintype "passive"))
      (node (ref "U8") (pin "8") (pinfunction "V+_8") (pintype "passive"))
    )
    (net (code "64") (name "GND") (class "Default")
      (node (ref "C1") (pin "2") (pinfunction "2_2") (pintype "passive"))
      (node (ref "C10") (pin "1") (pinfunction "1_1") (pintype "passive"))
      (node (ref "C14") (pin "1") (pinfunction "1_1") (pintype "passive"))
      (node (ref "C17") (pin "1") (pinfunction "1_1") (pintype "passive"))
      (node (ref "C18") (pin "1") (pinfunction "1_1") (pintype "passive"))
      (node (ref "C19") (pin "1") (pinfunction "1_1") (pintype "passive"))
      (node (ref "C2") (pin "2") (pinfunction "2_2") (pintype "passive"))
      (node (ref "C20") (pin "1") (pinfunction "1_1") (pintype "passive"))
      (node (ref "C21") (pin "1") (pinfunction "1_1") (pintype "passive"))
      (node (ref "C22") (pin "2") (pinfunction "2_2") (pintype "passive"))
      (node (ref "C27") (pin "2") (pinfunction "2_2") (pintype "passive"))
      (node (ref "C28") (pin "1") (pinfunction "1_1") (pintype "passive"))
      (node (ref "C3") (pin "2") (pinfunction "2_2") (pintype "passive"))
      (node (ref "C4") (pin "2") (pinfunction "2_2") (pintype "passive"))
      (node (ref "C5") (pin "2") (pinfunction "2_2") (pintype "passive"))
      (node (ref "C6") (pin "1") (pinfunction "1_1") (pintype "passive"))
      (node (ref "C7") (pin "2") (pinfunction "2_2") (pintype "passive"))
      (node (ref "C9") (pin "2") (pinfunction "2_2") (pintype "passive"))
      (node (ref "J1") (pin "1") (pinfunction "GND_1") (pintype "passive"))
      (node (ref "J1") (pin "34") (pinfunction "GND_34") (pintype "passive"))
      (node (ref "J1") (pin "35") (pinfunction "GND_35") (pintype "passive"))
      (node (ref "J1") (pin "36") (pinfunction "~{CD1}_36") (pintype "passive"))
      (node (ref "J1") (pin "57") (pinfunction "~{VS2}_57") (pintype "passive"))
      (node (ref "J1") (pin "67") (pinfunction "~{CD2}_67") (pintype "passive"))
      (node (ref "J1") (pin "68") (pinfunction "GND_68") (pintype "passive"))
      (node (ref "J2") (pin "1") (pintype "passive"))
      (node (ref "J2") (pin "2") (pintype "passive"))
      (node (ref "Q1") (pin "2") (pinfunction "E_2") (pintype "passive"))
      (node (ref "Q2") (pin "2") (pinfunction "E_2") (pintype "passive"))
      (node (ref "Q3") (pin "2") (pinfunction "E_2") (pintype "passive"))
      (node (ref "R12") (pin "1") (pinfunction "1_1") (pintype "passive"))
      (node (ref "R14") (pin "2") (pinfunction "2_2") (pintype "passive"))
      (node (ref "R2") (pin "1") (pinfunction "1_1") (pintype "passive"))
      (node (ref "R21") (pin "1") (pinfunction "1_1") (pintype "passive"))
      (node (ref "R26") (pin "1") (pinfunction "1_1") (pintype "passive"))
      (node (ref "R30") (pin "1") (pinfunction "1_1") (pintype "passive"))
      (node (ref "R31") (pin "1") (pinfunction "1_1") (pintype "passive"))
      (node (ref "RP1") (pin "1") (pintype "passive"))
      (node (ref "U1") (pin "7") (pinfunction "GND_7") (pintype "passive"))
      (node (ref "U2") (pin "15") (pinfunction "VSS_15") (pintype "passive"))
      (node (ref "U2") (pin "20") (pinfunction "VSS_20") (pintype "passive"))
      (node (ref "U2") (pin "32") (pinfunction "VSS_32") (pintype "passive"))
      (node (ref "U2") (pin "44") (pinfunction "VSS_44") (pintype "passive"))
      (node (ref "U2") (pin "5") (pinfunction "VSS_5") (pintype "passive"))
      (node (ref "U2") (pin "68") (pinfunction "VSS_68") (pintype "passive"))
      (node (ref "U2") (pin "77") (pinfunction "VSS_77") (pintype "passive"))
      (node (ref "U2") (pin "88") (pinfunction "VSS_88") (pintype "passive"))
      (node (ref "U3") (pin "5") (pinfunction "VSS_5") (pintype "passive"))
      (node (ref "U3") (pin "6") (pinfunction "ORG_6") (pintype "passive"))
      (node (ref "U4") (pin "11") (pinfunction "5A_11") (pintype "passive"))
      (node (ref "U4") (pin "13") (pinfunction "6A_13") (pintype "passive"))
      (node (ref "U4") (pin "3") (pinfunction "2A_3") (pintype "passive"))
      (node (ref "U4") (pin "7") (pinfunction "GND_7") (pintype "passive"))
      (node (ref "U5") (pin "1") (pinfunction "VSS_1") (pintype "passive"))
      (node (ref "U5") (pin "14") (pinfunction "VSS_14") (pintype "passive"))
      (node (ref "U5") (pin "16") (pinfunction "VSS_16") (pintype "passive"))
      (node (ref "U6") (pin "3") (pinfunction "GND_3") (pintype "passive"))
      (node (ref "U7") (pin "4") (pinfunction "V-_4") (pintype "passive"))
      (node (ref "U8") (pin "4") (pinfunction "V-_4") (pintype "passive"))
      (node (ref "UX1") (pin "2") (pinfunction "GND_2") (pintype "passive"))
    )
    (net (code "65") (name "Net-(C2-Pad1)") (class "Default")
      (node (ref "C2") (pin "1") (pinfunction "1_1") (pintype "passive"))
      (node (ref "R1") (pin "1") (pinfunction "1_1") (pintype "passive"))
      (node (ref "R8") (pin "2") (pinfunction "2_2") (pintype "passive"))
    )
    (net (code "66") (name "Net-(C8-Pad2)") (class "Default")
      (node (ref "C8") (pin "2") (pinfunction "2_2") (pintype "passive"))
      (node (ref "R18") (pin "2") (pinfunction "2_2") (pintype "passive"))
      (node (ref "R19") (pin "2") (pinfunction "2_2") (pintype "passive"))
    )
    (net (code "67") (name "Net-(C9-Pad1)") (class "Default")
      (node (ref "C9") (pin "1") (pinfunction "1_1") (pintype "passive"))
      (node (ref "R22") (pin "1") (pinfunction "1_1") (pintype "passive"))
    )
    (net (code "68") (name "Net-(C10-Pad2)") (class "Default")
      (node (ref "C10") (pin "2") (pinfunction "2_2") (pintype "passive"))
      (node (ref "R23") (pin "1") (pinfunction "1_1") (pintype "passive"))
    )
    (net (code "69") (name "Net-(C11-Pad1)") (class "Default")
      (node (ref "C11") (pin "1") (pinfunction "1_1") (pintype "passive"))
      (node (ref "RP1") (pin "3") (pintype "passive"))
    )
    (net (code "70") (name "Net-(C11-Pad2)") (class "Default")
      (node (ref "C11") (pin "2") (pinfunction "2_2") (pintype "passive"))
      (node (ref "R29") (pin "1") (pinfunction "1_1") (pintype "passive"))
      (node (ref "R30") (pin "2") (pinfunction "2_2") (pintype "passive"))
      (node (ref "U8") (pin "3") (pintype "passive"))
    )
    (net (code "71") (name "Net-(C12-Pad1)") (class "Default")
      (node (ref "C12") (pin "1") (pinfunction "1_1") (pintype "passive"))
      (node (ref "RP1") (pin "2") (pintype "passive"))
    )
    (net (code "72") (name "Net-(C12-Pad2)") (class "Default")
      (node (ref "C12") (pin "2") (pinfunction "2_2") (pintype "passive"))
      (node (ref "R31") (pin "2") (pinfunction "2_2") (pintype "passive"))
      (node (ref "R33") (pin "1") (pinfunction "1_1") (pintype "passive"))
      (node (ref "U8") (pin "5") (pintype "passive"))
    )
    (net (code "73") (name "Net-(C13-Pad1)") (class "Default")
      (node (ref "C13") (pin "1") (pinfunction "1_1") (pintype "passive"))
      (node (ref "C26") (pin "1") (pinfunction "1_1") (pintype "passive"))
      (node (ref "R25") (pin "2") (pinfunction "2_2") (pintype "passive"))
      (node (ref "U8") (pin "7") (pintype "passive"))
    )
    (net (code "74") (name "Net-(C13-Pad2)") (class "Default")
      (node (ref "C13") (pin "2") (pinfunction "2_2") (pintype "passive"))
      (node (ref "R27") (pin "2") (pinfunction "2_2") (pintype "passive"))
      (node (ref "R28") (pin "2") (pinfunction "2_2") (pintype "passive"))
    )
    (net (code "75") (name "Net-(C23-Pad1)") (class "Default")
      (node (ref "C23") (pin "1") (pinfunction "1_1") (pintype "passive"))
      (node (ref "J2") (pin "5") (pintype "passive"))
    )
    (net (code "76") (name "Net-(C23-Pad2)") (class "Default")
      (node (ref "C23") (pin "2") (pinfunction "2_2") (pintype "passive"))
      (node (ref "R16") (pin "2") (pinfunction "2_2") (pintype "passive"))
    )
    (net (code "77") (name "Net-(C24-Pad1)") (class "Default")
      (node (ref "C24") (pin "1") (pinfunction "1_1") (pintype "passive"))
      (node (ref "J2") (pin "6") (pintype "passive"))
    )
    (net (code "78") (name "Net-(C24-Pad2)") (class "Default")
      (node (ref "C24") (pin "2") (pinfunction "2_2") (pintype "passive"))
      (node (ref "R17") (pin "2") (pinfunction "2_2") (pintype "passive"))
    )
    (net (code "79") (name "Net-(C25-Pad1)") (class "Default")
      (node (ref "C25") (pin "1") (pinfunction "1_1") (pintype "passive"))
      (node (ref "C8") (pin "1") (pinfunction "1_1") (pintype "passive"))
      (node (ref "R24") (pin "2") (pinfunction "2_2") (pintype "passive"))
      (node (ref "U8") (pin "1") (pintype "passive"))
    )
    (net (code "80") (name "Net-(C25-Pad2)") (class "Default")
      (node (ref "C25") (pin "2") (pinfunction "2_2") (pintype "passive"))
      (node (ref "R22") (pin "2") (pinfunction "2_2") (pintype "passive"))
      (node (ref "R24") (pin "1") (pinfunction "1_1") (pintype "passive"))
      (node (ref "U8") (pin "2") (pintype "passive"))
    )
    (net (code "81") (name "Net-(C26-Pad2)") (class "Default")
      (node (ref "C26") (pin "2") (pinfunction "2_2") (pintype "passive"))
      (node (ref "R23") (pin "2") (pinfunction "2_2") (pintype "passive"))
      (node (ref "R25") (pin "1") (pinfunction "1_1") (pintype "passive"))
      (node (ref "U8") (pin "6") (pintype "passive"))
    )
    (net (code "82") (name "Net-(C28-Pad2)") (class "Default")
      (node (ref "C28") (pin "2") (pinfunction "2_2") (pintype "passive"))
      (node (ref "R5") (pin "2") (pinfunction "2_2") (pintype "passive"))
    )
    (net (code "83") (name "Net-(J1-WP{slash}~{IOIS16})") (class "Default")
      (node (ref "J1") (pin "33") (pinfunction "WP/~{IOIS16}_33") (pintype "passive"))
      (node (ref "U2") (pin "10") (pinfunction "PC_WP/~{IOIS16}/~{IOCS16}_10") (pintype "passive"))
    )
    (net (code "84") (name "Net-(LS1-Pad1)") (class "Default")
      (node (ref "LS1") (pin "1") (pinfunction "1_1") (pintype "passive"))
      (node (ref "LS1") (pin "1A") (pinfunction "1A_1A") (pintype "passive"))
      (node (ref "U7") (pin "1") (pintype "passive"))
      (node (ref "U7") (pin "2") (pintype "passive"))
    )
    (net (code "85") (name "Net-(Q1-B)") (class "Default")
      (node (ref "Q1") (pin "1") (pinfunction "B_1") (pintype "passive"))
      (node (ref "R10") (pin "1") (pinfunction "1_1") (pintype "passive"))
    )
    (net (code "86") (name "Net-(Q1-C)") (class "Default")
      (node (ref "J2") (pin "4") (pintype "passive"))
      (node (ref "Q1") (pin "3") (pinfunction "C_3") (pintype "passive"))
      (node (ref "R18") (pin "1") (pinfunction "1_1") (pintype "passive"))
      (node (ref "R19") (pin "1") (pinfunction "1_1") (pintype "passive"))
      (node (ref "R21") (pin "2") (pinfunction "2_2") (pintype "passive"))
    )
    (net (code "87") (name "Net-(Q2-B)") (class "Default")
      (node (ref "Q2") (pin "1") (pinfunction "B_1") (pintype "passive"))
      (node (ref "R3") (pin "1") (pinfunction "1_1") (pintype "passive"))
    )
    (net (code "88") (name "Net-(Q2-C)") (class "Default")
      (node (ref "J2") (pin "3") (pintype "passive"))
      (node (ref "Q2") (pin "3") (pinfunction "C_3") (pintype "passive"))
      (node (ref "R26") (pin "2") (pinfunction "2_2") (pintype "passive"))
      (node (ref "R27") (pin "1") (pinfunction "1_1") (pintype "passive"))
      (node (ref "R28") (pin "1") (pinfunction "1_1") (pintype "passive"))
    )
    (net (code "89") (name "Net-(Q3-B)") (class "Default")
      (node (ref "Q3") (pin "1") (pinfunction "B_1") (pintype "passive"))
      (node (ref "R11") (pin "1") (pinfunction "1_1") (pintype "passive"))
    )
    (net (code "90") (name "Net-(Q3-C)") (class "Default")
      (node (ref "LS1") (pin "2") (pinfunction "2_2") (pintype "passive"))
      (node (ref "LS1") (pin "2A") (pinfunction "2A_2A") (pintype "passive"))
      (node (ref "Q3") (pin "3") (pinfunction "C_3") (pintype "passive"))
    )
    (net (code "91") (name "Net-(R10-Pad2)") (class "Default")
      (node (ref "R10") (pin "2") (pinfunction "2_2") (pintype "passive"))
      (node (ref "R2") (pin "2") (pinfunction "2_2") (pintype "passive"))
      (node (ref "R3") (pin "2") (pinfunction "2_2") (pintype "passive"))
      (node (ref "R9") (pin "2") (pinfunction "2_2") (pintype "passive"))
    )
    (net (code "92") (name "Net-(R14-Pad1)") (class "Default")
      (node (ref "R14") (pin "1") (pinfunction "1_1") (pintype "passive"))
      (node (ref "R15") (pin "2") (pinfunction "2_2") (pintype "passive"))
      (node (ref "R16") (pin "1") (pinfunction "1_1") (pintype "passive"))
      (node (ref "R17") (pin "1") (pinfunction "1_1") (pintype "passive"))
      (node (ref "U7") (pin "5") (pintype "passive"))
    )
    (net (code "93") (name "Net-(R20-Pad1)") (class "Default")
      (node (ref "R20") (pin "1") (pinfunction "1_1") (pintype "passive"))
      (node (ref "R5") (pin "1") (pinfunction "1_1") (pintype "passive"))
      (node (ref "U7") (pin "6") (pintype "passive"))
    )
    (net (code "94") (name "Net-(R20-Pad2)") (class "Default")
      (node (ref "R20") (pin "2") (pinfunction "2_2") (pintype "passive"))
      (node (ref "U7") (pin "3") (pintype "passive"))
      (node (ref "U7") (pin "7") (pintype "passive"))
    )
    (net (code "95") (name "Net-(U1-1D)") (class "Default")
      (node (ref "U1") (pin "2") (pinfunction "1D_2") (pintype "passive"))
      (node (ref "U1") (pin "6") (pinfunction "1~{Q}_6") (pintype "passive"))
    )
    (net (code "96") (name "Net-(U1-1Q)") (class "Default")
      (node (ref "U1") (pin "5") (pinfunction "1Q_5") (pintype "passive"))
      (node (ref "U2") (pin "58") (pinfunction "PC_MCLK_IN_58") (pintype "passive"))
    )
    (net (code "97") (name "Net-(U1-2CLK)") (class "Default")
      (node (ref "U1") (pin "11") (pinfunction "2CLK_11") (pintype "passive"))
      (node (ref "U4") (pin "2") (pinfunction "1Y_2") (pintype "passive"))
    )
    (net (code "98") (name "Net-(U1-2Q)") (class "Default")
      (node (ref "U1") (pin "9") (pinfunction "2Q_9") (pintype "passive"))
      (node (ref "U5") (pin "11") (pinfunction "~{IC}_11") (pintype "passive"))
    )
    (net (code "99") (name "Net-(U1-2~{CLR})") (class "Default")
      (node (ref "U1") (pin "13") (pinfunction "2~{CLR}_13") (pintype "passive"))
      (node (ref "U2") (pin "11") (pinfunction "~{ATA}_HRESET_11") (pintype "passive"))
    )
    (net (code "100") (name "Net-(U2-EE_CS)") (class "Default")
      (node (ref "U2") (pin "52") (pinfunction "EE_CS_52") (pintype "passive"))
      (node (ref "U3") (pin "1") (pinfunction "S_1") (pintype "passive"))
    )
    (net (code "101") (name "Net-(U2-EE_D0)") (class "Default")
      (node (ref "U2") (pin "53") (pinfunction "EE_D0_53") (pintype "passive"))
      (node (ref "U3") (pin "3") (pinfunction "D_3") (pintype "passive"))
    )
    (net (code "102") (name "Net-(U2-EE_D1)") (class "Default")
      (node (ref "U2") (pin "54") (pinfunction "EE_D1_54") (pintype "passive"))
      (node (ref "U3") (pin "4") (pinfunction "Q_4") (pintype "passive"))
    )
    (net (code "103") (name "Net-(U2-EE_MASTER)") (class "Default")
      (node (ref "R7") (pin "1") (pinfunction "1_1") (pintype "passive"))
      (node (ref "U2") (pin "51") (pinfunction "EE_MASTER_51") (pintype "passive"))
    )
    (net (code "104") (name "Net-(U2-EE_SK)") (class "Default")
      (node (ref "U2") (pin "50") (pinfunction "EE_SK_50") (pintype "passive"))
      (node (ref "U3") (pin "2") (pinfunction "C_2") (pintype "passive"))
    )
    (net (code "105") (name "Net-(U2-EXTP_AUDIO)") (class "Default")
      (node (ref "R4") (pin "1") (pinfunction "1_1") (pintype "passive"))
      (node (ref "U2") (pin "60") (pinfunction "EXTP_AUDIO_60") (pintype "passive"))
    )
    (net (code "106") (name "Net-(U2-~{POR})") (class "Default")
      (node (ref "C19") (pin "2") (pinfunction "2_2") (pintype "passive"))
      (node (ref "U2") (pin "56") (pinfunction "~{POR}_56") (pintype "passive"))
    )
    (net (code "107") (name "Net-(U4-3A)") (class "Default")
      (node (ref "R1") (pin "2") (pinfunction "2_2") (pintype "passive"))
      (node (ref "U4") (pin "5") (pinfunction "3A_5") (pintype "passive"))
    )
    (net (code "108") (name "Net-(U4-3Y)") (class "Default")
      (node (ref "R9") (pin "1") (pinfunction "1_1") (pintype "passive"))
      (node (ref "U4") (pin "6") (pinfunction "3Y_6") (pintype "passive"))
    )
    (net (code "109") (name "Net-(U6-L.OUT)") (class "Default")
      (node (ref "RP1") (pin "4") (pintype "passive"))
      (node (ref "U6") (pin "4") (pinfunction "L.OUT_4") (pintype "passive"))
    )
    (net (code "110") (name "Net-(U6-R.OUT)") (class "Default")
      (node (ref "RP1") (pin "5") (pintype "passive"))
      (node (ref "U6") (pin "1") (pinfunction "R.OUT_1") (pintype "passive"))
    )
    (net (code "111") (name "Net-(U6-REF)") (class "Default")
      (node (ref "C5") (pin "1") (pinfunction "1_1") (pintype "passive"))
      (node (ref "U6") (pin "2") (pinfunction "REF_2") (pintype "passive"))
    )
    (net (code "112") (name "Net-(UX1-EN)") (class "Default")
      (node (ref "R12") (pin "2") (pinfunction "2_2") (pintype "passive"))
      (node (ref "UX1") (pin "1") (pinfunction "EN_1") (pintype "passive"))
    )
    (net (code "113") (name "unconnected-(J1-A11-Pad10)") (class "Default")
      (node (ref "J1") (pin "10") (pinfunction "A11_10") (pintype "passive+no_connect"))
    )
    (net (code "114") (name "unconnected-(J1-A12-Pad21)") (class "Default")
      (node (ref "J1") (pin "21") (pinfunction "A12_21") (pintype "passive+no_connect"))
    )
    (net (code "115") (name "unconnected-(J1-A13-Pad13)") (class "Default")
      (node (ref "J1") (pin "13") (pinfunction "A13_13") (pintype "passive+no_connect"))
    )
    (net (code "116") (name "unconnected-(J1-A14-Pad14)") (class "Default")
      (node (ref "J1") (pin "14") (pinfunction "A14_14") (pintype "passive+no_connect"))
    )
    (net (code "117") (name "unconnected-(J1-A15-Pad20)") (class "Default")
      (node (ref "J1") (pin "20") (pinfunction "A15_20") (pintype "passive+no_connect"))
    )
    (net (code "118") (name "unconnected-(J1-A16-Pad19)") (class "Default")
      (node (ref "J1") (pin "19") (pinfunction "A16_19") (pintype "passive+no_connect"))
    )
    (net (code "119") (name "unconnected-(J1-A17-Pad46)") (class "Default")
      (node (ref "J1") (pin "46") (pinfunction "A17_46") (pintype "passive+no_connect"))
    )
    (net (code "120") (name "unconnected-(J1-A18-Pad47)") (class "Default")
      (node (ref "J1") (pin "47") (pinfunction "A18_47") (pintype "passive+no_connect"))
    )
    (net (code "121") (name "unconnected-(J1-A19-Pad48)") (class "Default")
      (node (ref "J1") (pin "48") (pinfunction "A19_48") (pintype "passive+no_connect"))
    )
    (net (code "122") (name "unconnected-(J1-A20-Pad49)") (class "Default")
      (node (ref "J1") (pin "49") (pinfunction "A20_49") (pintype "passive+no_connect"))
    )
    (net (code "123") (name "unconnected-(J1-A21-Pad50)") (class "Default")
      (node (ref "J1") (pin "50") (pinfunction "A21_50") (pintype "passive+no_connect"))
    )
    (net (code "124") (name "unconnected-(J1-A22-Pad53)") (class "Default")
      (node (ref "J1") (pin "53") (pinfunction "A22_53") (pintype "passive+no_connect"))
    )
    (net (code "125") (name "unconnected-(J1-A23-Pad54)") (class "Default")
      (node (ref "J1") (pin "54") (pinfunction "A23_54") (pintype "passive+no_connect"))
    )
    (net (code "126") (name "unconnected-(J1-A24-Pad55)") (class "Default")
      (node (ref "J1") (pin "55") (pinfunction "A24_55") (pintype "passive+no_connect"))
    )
    (net (code "127") (name "unconnected-(J1-A25-Pad56)") (class "Default")
      (node (ref "J1") (pin "56") (pinfunction "A25_56") (pintype "passive+no_connect"))
    )
    (net (code "128") (name "unconnected-(J1-VPP1-Pad18)") (class "Default")
      (node (ref "J1") (pin "18") (pinfunction "VPP1_18") (pintype "passive+no_connect"))
    )
    (net (code "129") (name "unconnected-(J1-VPP2-Pad52)") (class "Default")
      (node (ref "J1") (pin "52") (pinfunction "VPP2_52") (pintype "passive+no_connect"))
    )
    (net (code "130") (name "unconnected-(J1-~{BVD2}{slash}SPKR-Pad62)") (class "Default")
      (node (ref "J1") (pin "62") (pinfunction "~{BVD2}/SPKR_62") (pintype "passive+no_connect"))
    )
    (net (code "131") (name "unconnected-(J1-~{VS1}-Pad43)") (class "Default")
      (node (ref "J1") (pin "43") (pinfunction "~{VS1}_43") (pintype "passive+no_connect"))
    )
    (net (code "132") (name "unconnected-(U1-2~{Q}-Pad8)") (class "Default")
      (node (ref "U1") (pin "8") (pinfunction "2~{Q}_8") (pintype "passive+no_connect"))
    )
    (net (code "133") (name "unconnected-(U2-ATA_DATA8{slash}RES1-Pad13)") (class "Default")
      (node (ref "U2") (pin "13") (pinfunction "ATA_DATA8/RES1_13") (pintype "passive+no_connect"))
    )
    (net (code "134") (name "unconnected-(U2-ATA_DATA9{slash}PACK_IN-Pad17)") (class "Default")
      (node (ref "U2") (pin "17") (pinfunction "ATA_DATA9/PACK_IN_17") (pintype "passive+no_connect"))
    )
    (net (code "135") (name "unconnected-(U2-ATA_DATA10-Pad19)") (class "Default")
      (node (ref "U2") (pin "19") (pinfunction "ATA_DATA10_19") (pintype "passive+no_connect"))
    )
    (net (code "136") (name "unconnected-(U2-ATA_DATA11-Pad22)") (class "Default")
      (node (ref "U2") (pin "22") (pinfunction "ATA_DATA11_22") (pintype "passive+no_connect"))
    )
    (net (code "137") (name "unconnected-(U2-ATA_DATA12-Pad25)") (class "Default")
      (node (ref "U2") (pin "25") (pinfunction "ATA_DATA12_25") (pintype "passive+no_connect"))
    )
    (net (code "138") (name "unconnected-(U2-ATA_DATA13-Pad27)") (class "Default")
      (node (ref "U2") (pin "27") (pinfunction "ATA_DATA13_27") (pintype "passive+no_connect"))
    )
    (net (code "139") (name "unconnected-(U2-ATA_DATA14-Pad29)") (class "Default")
      (node (ref "U2") (pin "29") (pinfunction "ATA_DATA14_29") (pintype "passive+no_connect"))
    )
    (net (code "140") (name "unconnected-(U2-ATA_DATA15-Pad31)") (class "Default")
      (node (ref "U2") (pin "31") (pinfunction "ATA_DATA15_31") (pintype "passive+no_connect"))
    )
    (net (code "141") (name "unconnected-(U2-ATA_HA2-Pad41)") (class "Default")
      (node (ref "U2") (pin "41") (pinfunction "ATA_HA2_41") (pintype "passive+no_connect"))
    )
    (net (code "142") (name "unconnected-(U2-ATA_HCS1-Pad43)") (class "Default")
      (node (ref "U2") (pin "43") (pinfunction "ATA_HCS1_43") (pintype "passive+no_connect"))
    )
    (net (code "143") (name "unconnected-(U2-ATA_IOCHRDY-Pad35)") (class "Default")
      (node (ref "U2") (pin "35") (pinfunction "ATA_IOCHRDY_35") (pintype "passive+no_connect"))
    )
    (net (code "144") (name "unconnected-(U2-EXTP_APWDN-Pad59)") (class "Default")
      (node (ref "U2") (pin "59") (pinfunction "EXTP_APWDN_59") (pintype "passive+no_connect"))
    )
    (net (code "145") (name "unconnected-(U2-EXTP_STSCHG{slash}RES2-Pad61)") (class "Default")
      (node (ref "U2") (pin "61") (pinfunction "EXTP_STSCHG/RES2_61") (pintype "passive+no_connect"))
    )
    (net (code "146") (name "unconnected-(U2-V_PINT-Pad57)") (class "Default")
      (node (ref "U2") (pin "57") (pinfunction "V_PINT_57") (pintype "passive+no_connect"))
    )
    (net (code "147") (name "unconnected-(U2-~{ATA}_DACK{slash}BVD2-Pad47)") (class "Default")
      (node (ref "U2") (pin "47") (pinfunction "~{ATA}_DACK/BVD2_47") (pintype "passive+no_connect"))
    )
    (net (code "148") (name "unconnected-(U2-~{ATA}_DREQ{slash}BVD1-Pad48)") (class "Default")
      (node (ref "U2") (pin "48") (pinfunction "~{ATA}_DREQ/BVD1_48") (pintype "passive+no_connect"))
    )
    (net (code "149") (name "unconnected-(U2-~{ATA}_IOCS16-Pad37)") (class "Default")
      (node (ref "U2") (pin "37") (pinfunction "~{ATA}_IOCS16_37") (pintype "passive+no_connect"))
    )
    (net (code "150") (name "unconnected-(U2-~{ATA}_MRD-Pad49)") (class "Default")
      (node (ref "U2") (pin "49") (pinfunction "~{ATA}_MRD_49") (pintype "passive+no_connect"))
    )
    (net (code "151") (name "unconnected-(U2-~{ATA}_MWR-Pad55)") (class "Default")
      (node (ref "U2") (pin "55") (pinfunction "~{ATA}_MWR_55") (pintype "passive+no_connect"))
    )
    (net (code "152") (name "unconnected-(U2-~{ATA}_PDASP{slash}EXTP_WP-Pad46)") (class "Default")
      (node (ref "U2") (pin "46") (pinfunction "~{ATA}_PDASP/EXTP_WP_46") (pintype "passive+no_connect"))
    )
    (net (code "153") (name "unconnected-(U2-~{ATA}_PDIAG{slash}ATA_BHE{slash}RING_IN-Pad45)") (class "Default")
      (node (ref "U2") (pin "45") (pinfunction "~{ATA}_PDIAG/ATA_BHE/RING_IN_45") (pintype "passive+no_connect"))
    )
    (net (code "154") (name "unconnected-(U3-DU-Pad7)") (class "Default")
      (node (ref "U3") (pin "7") (pinfunction "DU_7") (pintype "passive+no_connect"))
    )
    (net (code "155") (name "unconnected-(U4-2Y-Pad4)") (class "Default")
      (node (ref "U4") (pin "4") (pinfunction "2Y_4") (pintype "passive+no_connect"))
    )
    (net (code "156") (name "unconnected-(U4-5Y-Pad10)") (class "Default")
      (node (ref "U4") (pin "10") (pinfunction "5Y_10") (pintype "passive+no_connect"))
    )
    (net (code "157") (name "unconnected-(U4-6Y-Pad12)") (class "Default")
      (node (ref "U4") (pin "12") (pinfunction "6Y_12") (pintype "passive+no_connect"))
    )
    (net (code "158") (name "unconnected-(U5-NC-Pad10)") (class "Default")
      (node (ref "U5") (pin "10") (pinfunction "NC_10") (pintype "passive+no_connect"))
    )
    (net (code "159") (name "unconnected-(U5-NC-Pad13)") (class "Default")
      (node (ref "U5") (pin "13") (pinfunction "NC_13") (pintype "passive+no_connect"))
    )
  )
)
